# 01_POWER.net
KiCad netlist of a schematic drawn in Altium Designer
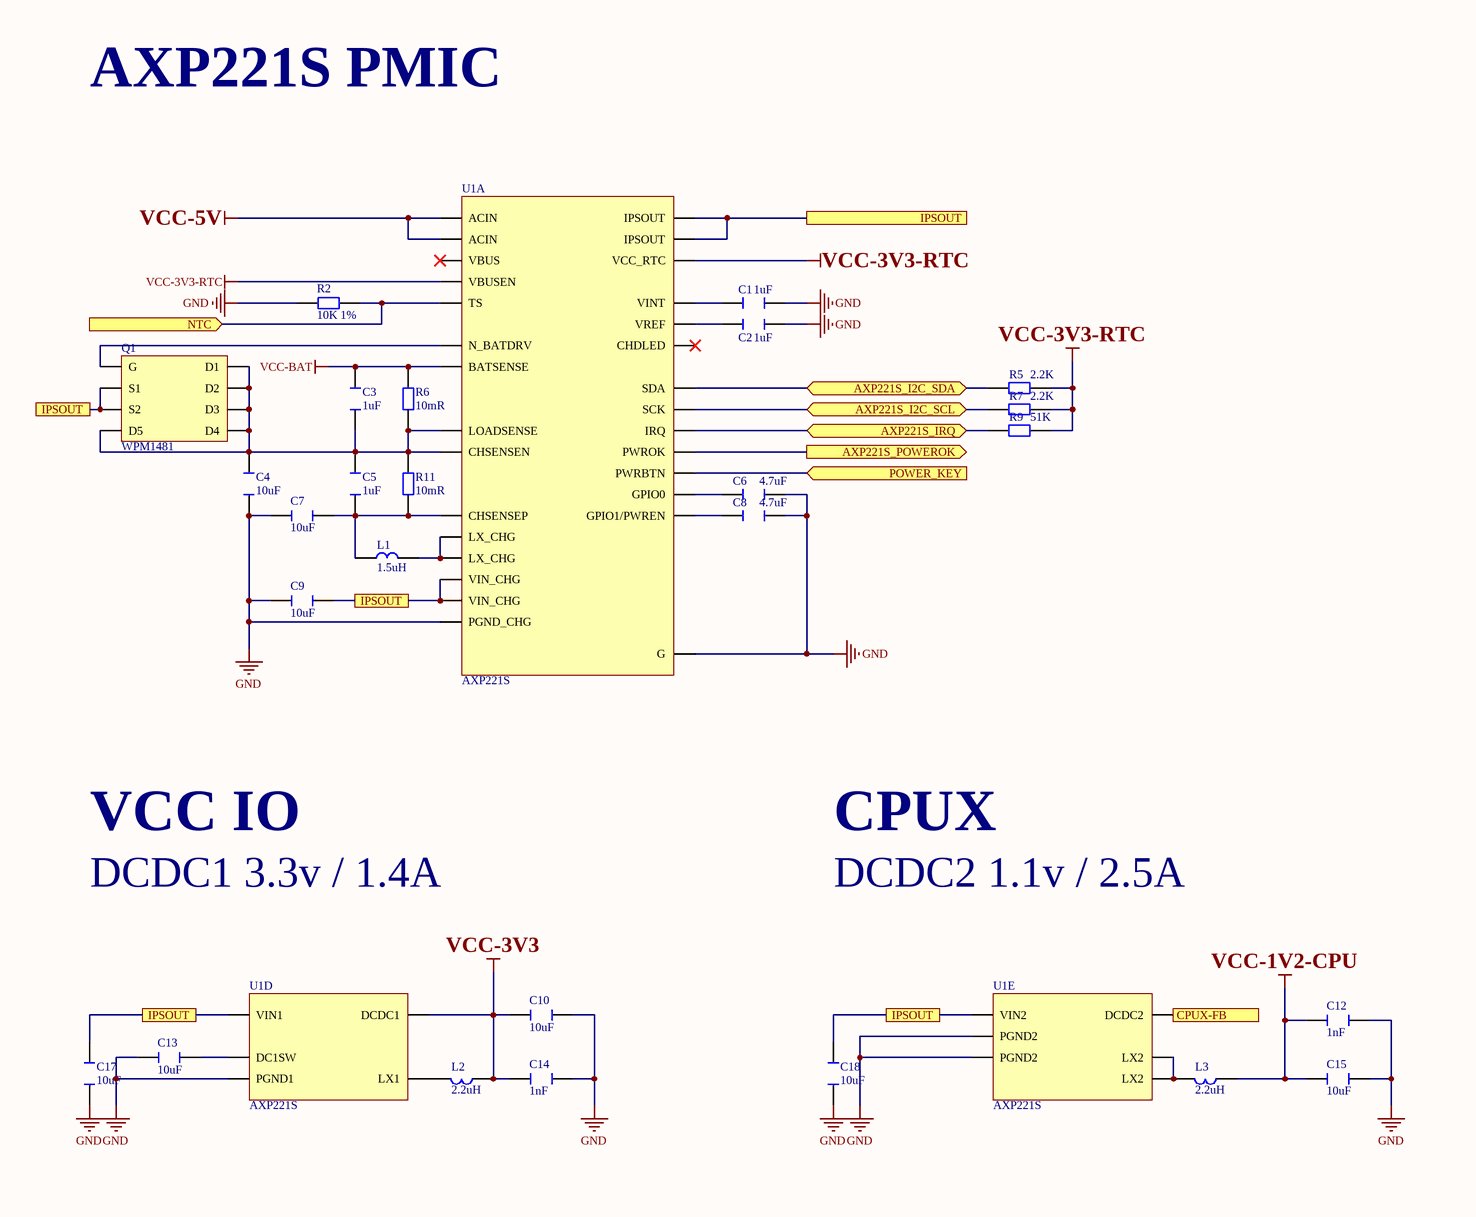
[diagram p0: 01_POWER.SchDoc, top left]
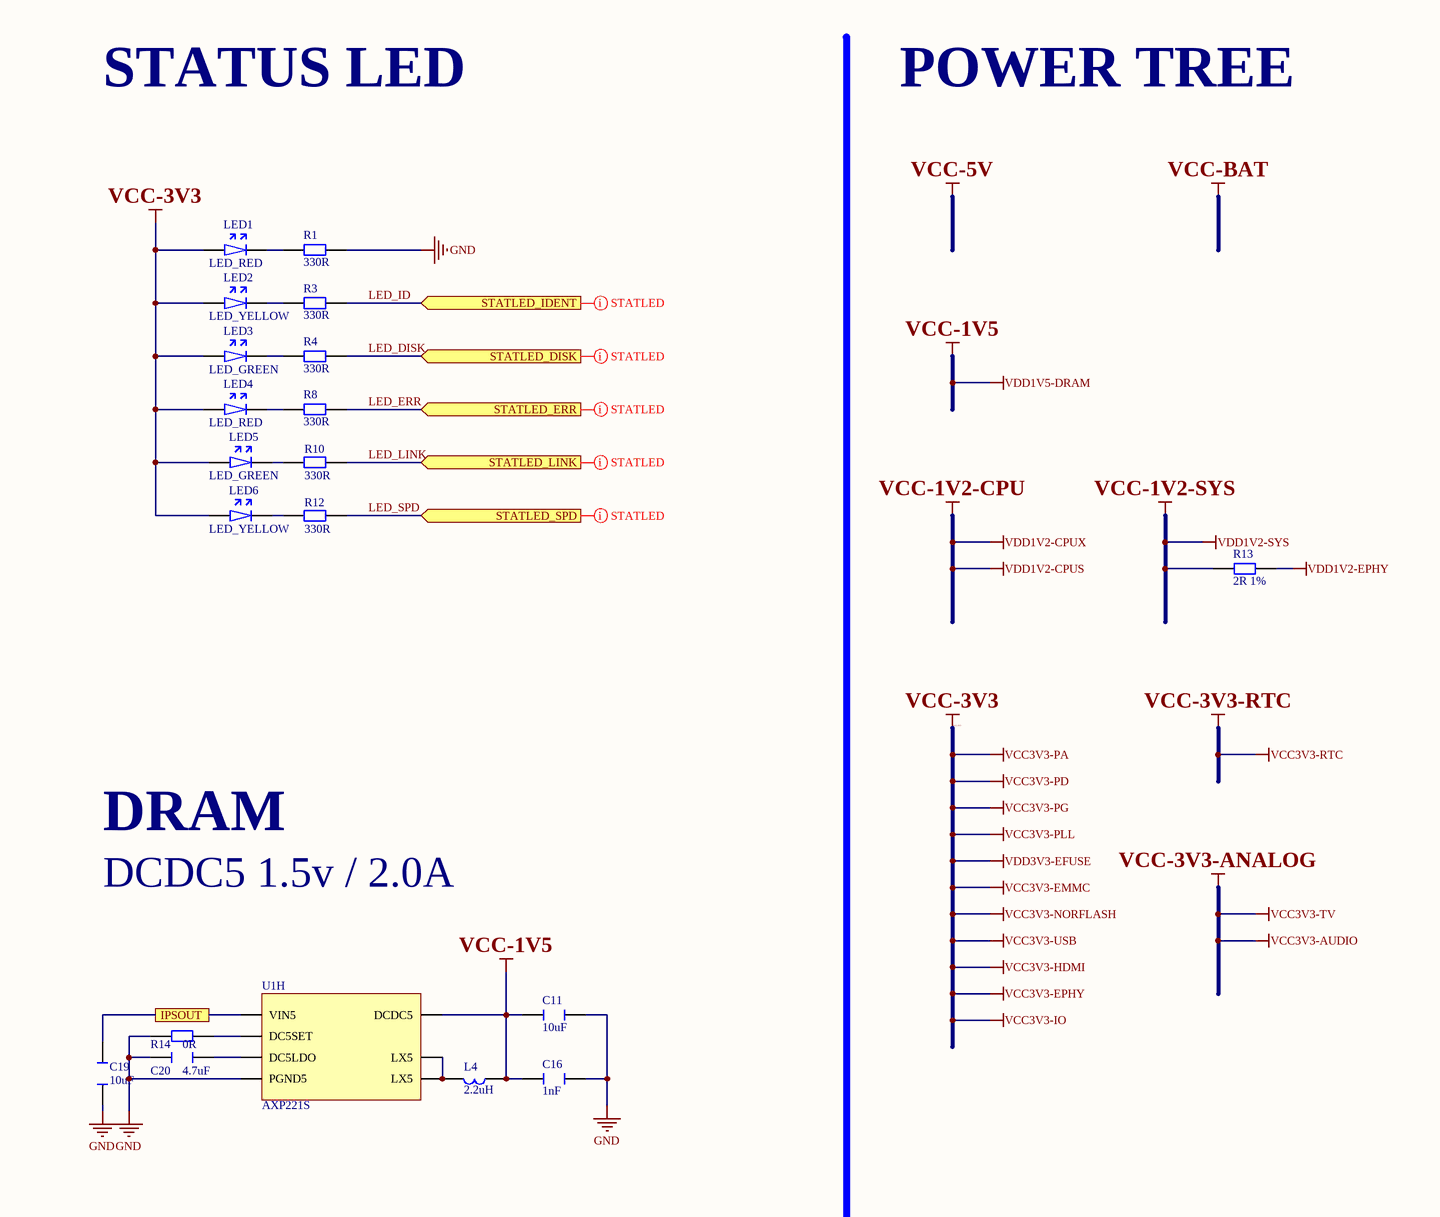
[diagram p1: 01_POWER.SchDoc, top right]
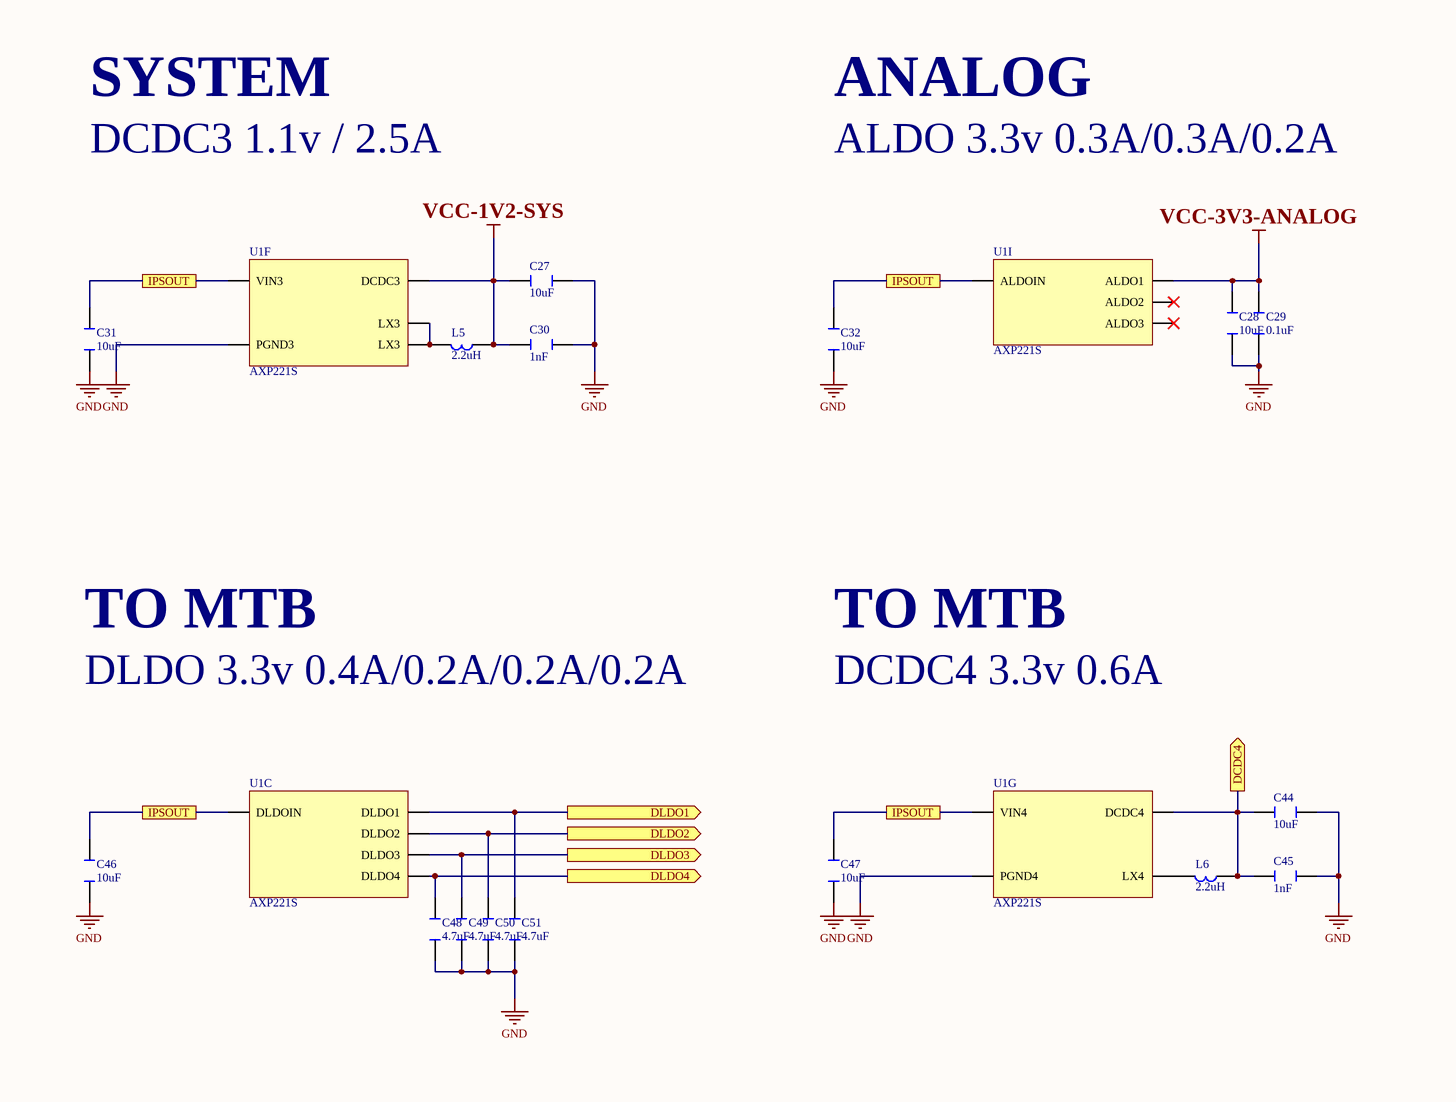
[diagram p2: 01_POWER.SchDoc, bottom left]
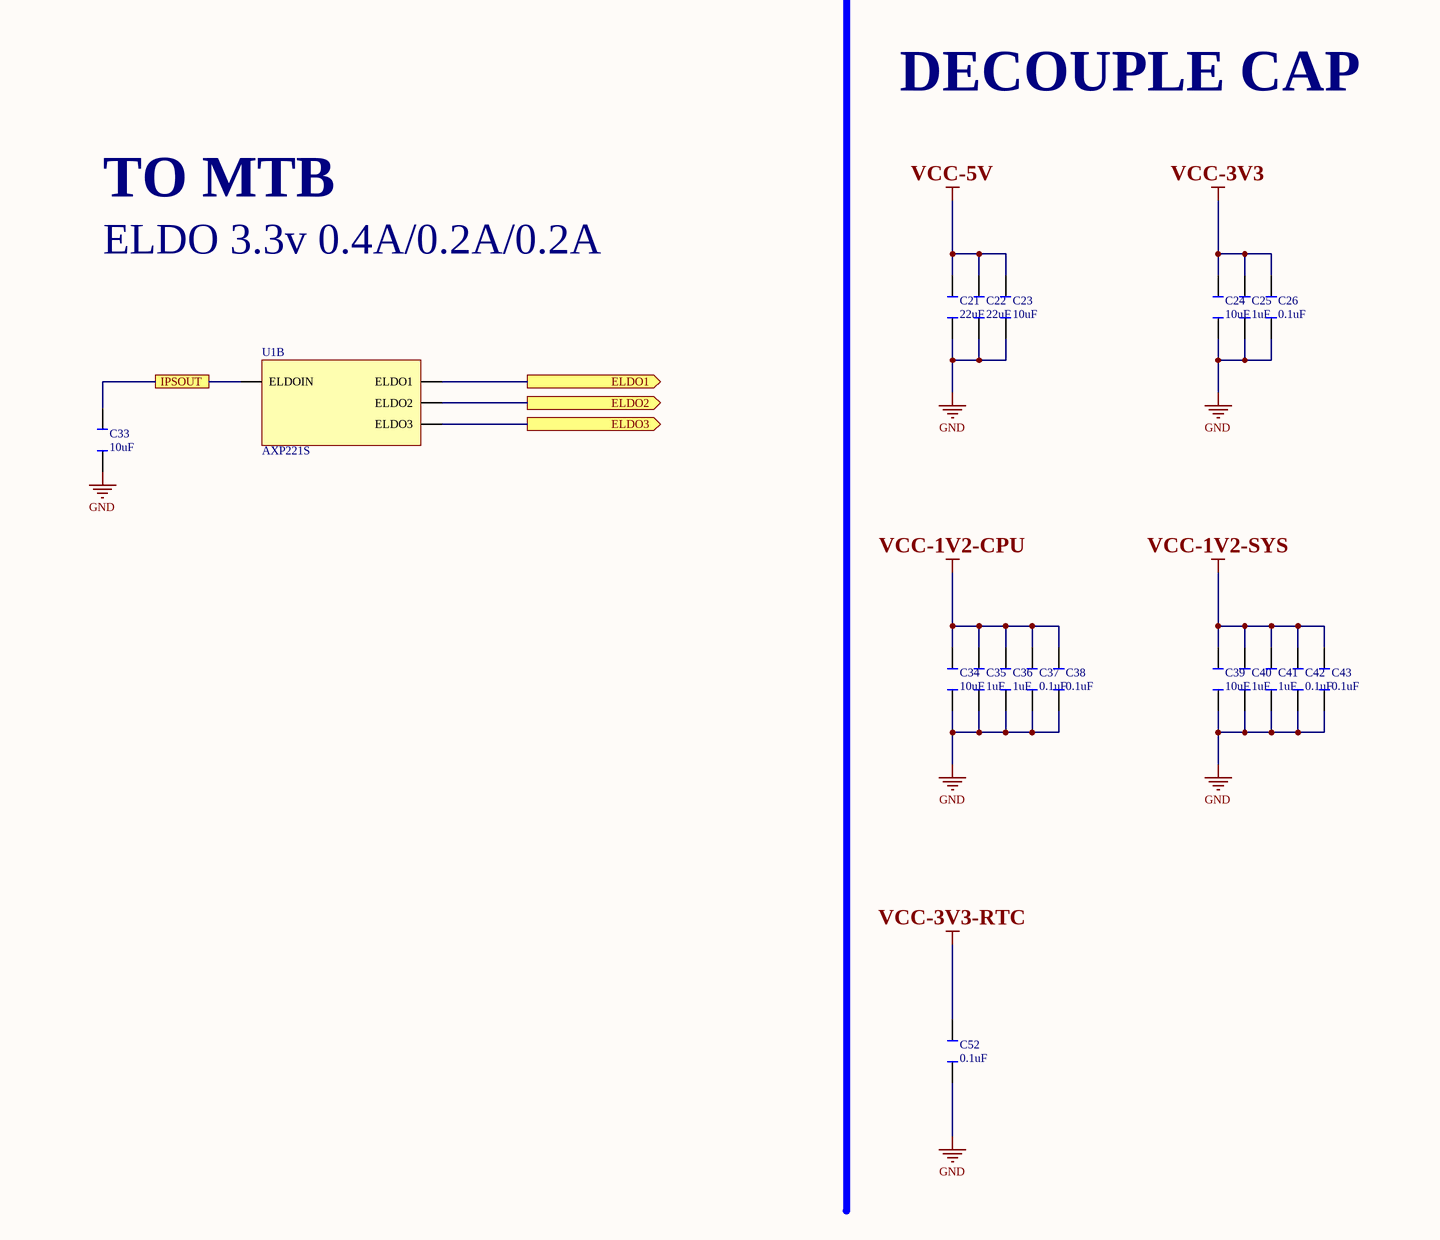
[diagram p3: 01_POWER.SchDoc, bottom right]

(export (version "E")
  (design (tool "Eeschema 10.0.6"))
  (components
    (comp (ref "C1") (value "1uF") (footprint "C0603") (libsource (lib "Board") (part "C_1UF")))
    (comp (ref "C2") (value "1uF") (footprint "C0603") (libsource (lib "Board") (part "C_1UF")))
    (comp (ref "C3") (value "1uF") (footprint "C0603") (libsource (lib "Board") (part "C_1UF")))
    (comp (ref "C4") (value "10uF") (footprint "C0603") (libsource (lib "Board") (part "C_10UF")))
    (comp (ref "C5") (value "1uF") (footprint "C0603") (libsource (lib "Board") (part "C_1UF")))
    (comp (ref "C6") (value "4.7uF") (footprint "C0402") (libsource (lib "Board") (part "C_4.7UF")))
    (comp (ref "C7") (value "10uF") (footprint "C0603") (libsource (lib "Board") (part "C_10UF")))
    (comp (ref "C8") (value "4.7uF") (footprint "C0402") (libsource (lib "Board") (part "C_4.7UF")))
    (comp (ref "C9") (value "10uF") (footprint "C0603") (libsource (lib "Board") (part "C_10UF")))
    (comp (ref "C10") (value "10uF") (footprint "C0603") (libsource (lib "Board") (part "C_10UF")))
    (comp (ref "C11") (value "10uF") (footprint "C0603") (libsource (lib "Board") (part "C_10UF")))
    (comp (ref "C12") (value "1nF") (footprint "C0603") (libsource (lib "Board") (part "C_1NF")))
    (comp (ref "C13") (value "10uF") (footprint "C0603") (libsource (lib "Board") (part "C_10UF")))
    (comp (ref "C14") (value "1nF") (footprint "C0603") (libsource (lib "Board") (part "C_1NF")))
    (comp (ref "C15") (value "10uF") (footprint "C0603") (libsource (lib "Board") (part "C_10UF")))
    (comp (ref "C16") (value "1nF") (footprint "C0603") (libsource (lib "Board") (part "C_1NF")))
    (comp (ref "C17") (value "10uF") (footprint "C0603") (libsource (lib "Board") (part "C_10UF")))
    (comp (ref "C18") (value "10uF") (footprint "C0603") (libsource (lib "Board") (part "C_10UF")))
    (comp (ref "C19") (value "10uF") (footprint "C0603") (libsource (lib "Board") (part "C_10UF")))
    (comp (ref "C20") (value "4.7uF") (footprint "C0603") (libsource (lib "Board") (part "C_4.7UF")))
    (comp (ref "C21") (value "22uF") (footprint "C0603") (libsource (lib "Board") (part "C_22UF")))
    (comp (ref "C22") (value "22uF") (footprint "C0603") (libsource (lib "Board") (part "C_22UF")))
    (comp (ref "C23") (value "10uF") (footprint "C0603") (libsource (lib "Board") (part "C_10UF")))
    (comp (ref "C24") (value "10uF") (footprint "C0603") (libsource (lib "Board") (part "C_10UF")))
    (comp (ref "C25") (value "1uF") (footprint "C0402") (libsource (lib "Board") (part "C_1UF")))
    (comp (ref "C26") (value "0.1uF") (footprint "C0603") (libsource (lib "Board") (part "C_0.1UF")))
    (comp (ref "C27") (value "10uF") (footprint "C0603") (libsource (lib "Board") (part "C_10UF")))
    (comp (ref "C28") (value "10uF") (footprint "C0603") (libsource (lib "Board") (part "C_10UF")))
    (comp (ref "C29") (value "0.1uF") (footprint "C0603") (libsource (lib "Board") (part "C_0.1UF")))
    (comp (ref "C30") (value "1nF") (footprint "C0603") (libsource (lib "Board") (part "C_1NF")))
    (comp (ref "C31") (value "10uF") (footprint "C0603") (libsource (lib "Board") (part "C_10UF")))
    (comp (ref "C32") (value "10uF") (footprint "C0603") (libsource (lib "Board") (part "C_10UF")))
    (comp (ref "C33") (value "10uF") (footprint "C0603") (libsource (lib "Board") (part "C_10UF")))
    (comp (ref "C34") (value "10uF") (footprint "C0603") (libsource (lib "Board") (part "C_10UF")))
    (comp (ref "C35") (value "1uF") (footprint "C0603") (libsource (lib "Board") (part "C_1UF")))
    (comp (ref "C36") (value "1uF") (footprint "C0603") (libsource (lib "Board") (part "C_1UF")))
    (comp (ref "C37") (value "0.1uF") (footprint "C0402") (libsource (lib "Board") (part "C_0.1UF")))
    (comp (ref "C38") (value "0.1uF") (footprint "C0402") (libsource (lib "Board") (part "C_0.1UF")))
    (comp (ref "C39") (value "10uF") (footprint "C0603") (libsource (lib "Board") (part "C_10UF")))
    (comp (ref "C40") (value "1uF") (footprint "C0402") (libsource (lib "Board") (part "C_1UF")))
    (comp (ref "C41") (value "1uF") (footprint "C0603") (libsource (lib "Board") (part "C_1UF")))
    (comp (ref "C42") (value "0.1uF") (footprint "C0402") (libsource (lib "Board") (part "C_0.1UF")))
    (comp (ref "C43") (value "0.1uF") (footprint "C0402") (libsource (lib "Board") (part "C_0.1UF")))
    (comp (ref "C44") (value "10uF") (footprint "C0603") (libsource (lib "Board") (part "C_10UF")))
    (comp (ref "C45") (value "1nF") (footprint "C0603") (libsource (lib "Board") (part "C_1NF")))
    (comp (ref "C46") (value "10uF") (footprint "C0603") (libsource (lib "Board") (part "C_10UF")))
    (comp (ref "C47") (value "10uF") (footprint "C0603") (libsource (lib "Board") (part "C_10UF")))
    (comp (ref "C48") (value "4.7uF") (footprint "C0603") (libsource (lib "Board") (part "C_4.7UF")))
    (comp (ref "C49") (value "4.7uF") (footprint "C0603") (libsource (lib "Board") (part "C_4.7UF")))
    (comp (ref "C50") (value "4.7uF") (footprint "C0603") (libsource (lib "Board") (part "C_4.7UF")))
    (comp (ref "C51") (value "4.7uF") (footprint "C0603") (libsource (lib "Board") (part "C_4.7UF")))
    (comp (ref "C52") (value "0.1uF") (footprint "C0402") (libsource (lib "Board") (part "C_0.1UF")))
    (comp (ref "L1") (value "1.5uH") (footprint "L2520") (libsource (lib "Board") (part "L_1.5UH")))
    (comp (ref "L2") (value "2.2uH") (footprint "L2520") (libsource (lib "Board") (part "L_2.2UH")))
    (comp (ref "L3") (value "2.2uH") (footprint "L2520") (libsource (lib "Board") (part "L_2.2UH")))
    (comp (ref "L4") (value "2.2uH") (footprint "L2520") (libsource (lib "Board") (part "L_2.2UH")))
    (comp (ref "L5") (value "2.2uH") (footprint "L2520") (libsource (lib "Board") (part "L_2.2UH")))
    (comp (ref "L6") (value "2.2uH") (footprint "L2520") (libsource (lib "Board") (part "L_2.2UH")))
    (comp (ref "LED1") (value "LED_RED") (footprint "LED0603_RED") (libsource (lib "Board") (part "LED_RED")))
    (comp (ref "LED2")
      (value "LED_YELLOW")
      (footprint "LED0603_YELLOW")
      (libsource (lib "Board") (part "LED_YELLOW"))
    )
    (comp (ref "LED3")
      (value "LED_GREEN")
      (footprint "LED0603_GREEN")
      (libsource (lib "Board") (part "LED_GREEN"))
    )
    (comp (ref "LED4") (value "LED_RED") (footprint "LED0603_RED") (libsource (lib "Board") (part "LED_RED")))
    (comp (ref "LED5")
      (value "LED_GREEN")
      (footprint "LED0603_GREEN")
      (libsource (lib "Board") (part "LED_GREEN"))
    )
    (comp (ref "LED6")
      (value "LED_YELLOW")
      (footprint "LED0603_YELLOW")
      (libsource (lib "Board") (part "LED_YELLOW"))
    )
    (comp (ref "Q1") (value "WPM1481") (footprint "WPM1481") (libsource (lib "Board") (part "WPM1481")))
    (comp (ref "R1") (value "330R") (footprint "R0402") (libsource (lib "Board") (part "R_330R")))
    (comp (ref "R2") (value "10K 1%") (footprint "R0402") (libsource (lib "Board") (part "R_10K_P1")))
    (comp (ref "R3") (value "330R") (footprint "R0402") (libsource (lib "Board") (part "R_330R")))
    (comp (ref "R4") (value "330R") (footprint "R0402") (libsource (lib "Board") (part "R_330R")))
    (comp (ref "R5") (value "2.2K") (footprint "R0402") (libsource (lib "Board") (part "R_2.2K")))
    (comp (ref "R6") (value "10mR") (footprint "R0805") (libsource (lib "Board") (part "R_10mR")))
    (comp (ref "R7") (value "2.2K") (footprint "R0402") (libsource (lib "Board") (part "R_2.2K")))
    (comp (ref "R8") (value "330R") (footprint "R0402") (libsource (lib "Board") (part "R_330R")))
    (comp (ref "R9") (value "51K") (footprint "R0402") (libsource (lib "Board") (part "R_51K")))
    (comp (ref "R10") (value "330R") (footprint "R0402") (libsource (lib "Board") (part "R_330R")))
    (comp (ref "R11") (value "10mR") (footprint "R0805") (libsource (lib "Board") (part "R_10mR")))
    (comp (ref "R12") (value "330R") (footprint "R0402") (libsource (lib "Board") (part "R_330R")))
    (comp (ref "R13") (value "2R 1%") (footprint "R0402") (libsource (lib "Board") (part "R_2R_P1")))
    (comp (ref "R14") (value "0R") (footprint "R0402") (libsource (lib "Board") (part "R_0R")))
    (comp (ref "U1") (value "AXP221S") (footprint "AXP221S") (libsource (lib "Board") (part "AXP221S")))
  )
  (nets
    (net (code "1") (name "/AXP221S_I2C_SCL") (class "Default")
      (node (ref "R7") (pin "1") (pinfunction "17_1") (pintype "passive"))
      (node (ref "U1") (pin "44") (pinfunction "SCK_44") (pintype "passive"))
    )
    (net (code "2") (name "/AXP221S_I2C_SDA") (class "Default")
      (node (ref "R5") (pin "1") (pinfunction "17_1") (pintype "passive"))
      (node (ref "U1") (pin "45") (pinfunction "SDA_45") (pintype "passive"))
    )
    (net (code "3") (name "/AXP221S_IRQ") (class "Default")
      (node (ref "R9") (pin "1") (pinfunction "17_1") (pintype "passive"))
      (node (ref "U1") (pin "29") (pinfunction "IRQ_29") (pintype "passive"))
    )
    (net (code "4") (name "/AXP221S_POWEROK") (class "Default")
      (node (ref "U1") (pin "43") (pinfunction "PWROK_43") (pintype "passive"))
    )
    (net (code "5") (name "/CPUX-FB") (class "Default")
      (node (ref "U1") (pin "28") (pinfunction "DCDC2_28") (pintype "passive"))
    )
    (net (code "6") (name "/DCDC4") (class "Default")
      (node (ref "C44") (pin "1") (pinfunction "17_1") (pintype "passive"))
      (node (ref "C45") (pin "1") (pinfunction "17_1") (pintype "passive"))
      (node (ref "L6") (pin "1") (pinfunction "17_1") (pintype "passive"))
      (node (ref "U1") (pin "67") (pinfunction "DCDC4_67") (pintype "passive"))
    )
    (net (code "7") (name "/DLDO1") (class "Default")
      (node (ref "C51") (pin "2") (pinfunction "18_2") (pintype "passive"))
      (node (ref "U1") (pin "19") (pinfunction "DLDO1_19") (pintype "passive"))
    )
    (net (code "8") (name "/DLDO2") (class "Default")
      (node (ref "C50") (pin "2") (pinfunction "18_2") (pintype "passive"))
      (node (ref "U1") (pin "17") (pinfunction "DLDO2_17") (pintype "passive"))
    )
    (net (code "9") (name "/DLDO3") (class "Default")
      (node (ref "C49") (pin "2") (pinfunction "18_2") (pintype "passive"))
      (node (ref "U1") (pin "16") (pinfunction "DLDO3_16") (pintype "passive"))
    )
    (net (code "10") (name "/DLDO4") (class "Default")
      (node (ref "C48") (pin "2") (pinfunction "18_2") (pintype "passive"))
      (node (ref "U1") (pin "20") (pinfunction "DLDO4_20") (pintype "passive"))
    )
    (net (code "11") (name "/ELDO1") (class "Default")
      (node (ref "U1") (pin "68") (pinfunction "ELDO1_68") (pintype "passive"))
    )
    (net (code "12") (name "/ELDO2") (class "Default")
      (node (ref "U1") (pin "2") (pinfunction "ELDO2_2") (pintype "passive"))
    )
    (net (code "13") (name "/ELDO3") (class "Default")
      (node (ref "U1") (pin "3") (pinfunction "ELDO3_3") (pintype "passive"))
    )
    (net (code "14") (name "/IPSOUT") (class "Default")
      (node (ref "C17") (pin "1") (pinfunction "17_1") (pintype "passive"))
      (node (ref "C18") (pin "1") (pinfunction "17_1") (pintype "passive"))
      (node (ref "C19") (pin "1") (pinfunction "17_1") (pintype "passive"))
      (node (ref "C31") (pin "1") (pinfunction "17_1") (pintype "passive"))
      (node (ref "C32") (pin "1") (pinfunction "17_1") (pintype "passive"))
      (node (ref "C33") (pin "1") (pinfunction "17_1") (pintype "passive"))
      (node (ref "C46") (pin "1") (pinfunction "17_1") (pintype "passive"))
      (node (ref "C47") (pin "1") (pinfunction "17_1") (pintype "passive"))
      (node (ref "C9") (pin "2") (pinfunction "18_2") (pintype "passive"))
      (node (ref "Q1") (pin "4") (pinfunction "S1_4") (pintype "passive"))
      (node (ref "Q1") (pin "7") (pinfunction "S2_7") (pintype "passive"))
      (node (ref "U1") (pin "1") (pinfunction "ELDOIN_1") (pintype "passive"))
      (node (ref "U1") (pin "13") (pinfunction "VIN1_13") (pintype "passive"))
      (node (ref "U1") (pin "18") (pinfunction "DLDOIN_18") (pintype "passive"))
      (node (ref "U1") (pin "23") (pinfunction "VIN2_23") (pintype "passive"))
      (node (ref "U1") (pin "33") (pinfunction "ALDOIN_33") (pintype "passive"))
      (node (ref "U1") (pin "39") (pinfunction "VIN3_39") (pintype "passive"))
      (node (ref "U1") (pin "53") (pinfunction "IPSOUT_53") (pintype "passive"))
      (node (ref "U1") (pin "54") (pinfunction "IPSOUT_54") (pintype "passive"))
      (node (ref "U1") (pin "62") (pinfunction "VIN_CHG_62") (pintype "passive"))
      (node (ref "U1") (pin "63") (pinfunction "VIN_CHG_63") (pintype "passive"))
      (node (ref "U1") (pin "64") (pinfunction "VIN4_64") (pintype "passive"))
      (node (ref "U1") (pin "9") (pinfunction "VIN5_9") (pintype "passive"))
    )
    (net (code "15") (name "/LED_DISK") (class "Default")
      (node (ref "R4") (pin "2") (pinfunction "18_2") (pintype "passive"))
    )
    (net (code "16") (name "/LED_ERR") (class "Default")
      (node (ref "R8") (pin "2") (pinfunction "18_2") (pintype "passive"))
    )
    (net (code "17") (name "/LED_ID") (class "Default")
      (node (ref "R3") (pin "2") (pinfunction "18_2") (pintype "passive"))
    )
    (net (code "18") (name "/LED_LINK") (class "Default")
      (node (ref "R10") (pin "1") (pinfunction "17_1") (pintype "passive"))
    )
    (net (code "19") (name "/LED_SPD") (class "Default")
      (node (ref "R12") (pin "1") (pinfunction "17_1") (pintype "passive"))
    )
    (net (code "20") (name "/NTC") (class "Default")
      (node (ref "R2") (pin "2") (pinfunction "18_2") (pintype "passive"))
      (node (ref "U1") (pin "30") (pinfunction "TS_30") (pintype "passive"))
    )
    (net (code "21") (name "/POWER_KEY") (class "Default")
      (node (ref "U1") (pin "12") (pinfunction "PWRBTN_12") (pintype "passive"))
    )
    (net (code "22") (name "GND") (class "Default")
      (node (ref "C1") (pin "2") (pinfunction "18_2") (pintype "passive"))
      (node (ref "C10") (pin "2") (pinfunction "18_2") (pintype "passive"))
      (node (ref "C11") (pin "2") (pinfunction "18_2") (pintype "passive"))
      (node (ref "C12") (pin "2") (pinfunction "18_2") (pintype "passive"))
      (node (ref "C13") (pin "1") (pinfunction "17_1") (pintype "passive"))
      (node (ref "C14") (pin "1") (pinfunction "17_1") (pintype "passive"))
      (node (ref "C15") (pin "2") (pinfunction "18_2") (pintype "passive"))
      (node (ref "C16") (pin "2") (pinfunction "18_2") (pintype "passive"))
      (node (ref "C17") (pin "2") (pinfunction "18_2") (pintype "passive"))
      (node (ref "C18") (pin "2") (pinfunction "18_2") (pintype "passive"))
      (node (ref "C19") (pin "2") (pinfunction "18_2") (pintype "passive"))
      (node (ref "C2") (pin "2") (pinfunction "18_2") (pintype "passive"))
      (node (ref "C20") (pin "2") (pinfunction "18_2") (pintype "passive"))
      (node (ref "C21") (pin "1") (pinfunction "17_1") (pintype "passive"))
      (node (ref "C22") (pin "1") (pinfunction "17_1") (pintype "passive"))
      (node (ref "C23") (pin "1") (pinfunction "17_1") (pintype "passive"))
      (node (ref "C24") (pin "1") (pinfunction "17_1") (pintype "passive"))
      (node (ref "C25") (pin "1") (pinfunction "17_1") (pintype "passive"))
      (node (ref "C26") (pin "1") (pinfunction "17_1") (pintype "passive"))
      (node (ref "C27") (pin "2") (pinfunction "18_2") (pintype "passive"))
      (node (ref "C28") (pin "2") (pinfunction "18_2") (pintype "passive"))
      (node (ref "C29") (pin "1") (pinfunction "17_1") (pintype "passive"))
      (node (ref "C30") (pin "2") (pinfunction "18_2") (pintype "passive"))
      (node (ref "C31") (pin "2") (pinfunction "18_2") (pintype "passive"))
      (node (ref "C32") (pin "2") (pinfunction "18_2") (pintype "passive"))
      (node (ref "C33") (pin "2") (pinfunction "18_2") (pintype "passive"))
      (node (ref "C34") (pin "1") (pinfunction "17_1") (pintype "passive"))
      (node (ref "C35") (pin "1") (pinfunction "17_1") (pintype "passive"))
      (node (ref "C36") (pin "1") (pinfunction "17_1") (pintype "passive"))
      (node (ref "C37") (pin "1") (pinfunction "17_1") (pintype "passive"))
      (node (ref "C38") (pin "1") (pinfunction "17_1") (pintype "passive"))
      (node (ref "C39") (pin "1") (pinfunction "17_1") (pintype "passive"))
      (node (ref "C4") (pin "1") (pinfunction "17_1") (pintype "passive"))
      (node (ref "C40") (pin "1") (pinfunction "17_1") (pintype "passive"))
      (node (ref "C41") (pin "1") (pinfunction "17_1") (pintype "passive"))
      (node (ref "C42") (pin "1") (pinfunction "17_1") (pintype "passive"))
      (node (ref "C43") (pin "1") (pinfunction "17_1") (pintype "passive"))
      (node (ref "C44") (pin "2") (pinfunction "18_2") (pintype "passive"))
      (node (ref "C45") (pin "2") (pinfunction "18_2") (pintype "passive"))
      (node (ref "C46") (pin "2") (pinfunction "18_2") (pintype "passive"))
      (node (ref "C47") (pin "2") (pinfunction "18_2") (pintype "passive"))
      (node (ref "C48") (pin "1") (pinfunction "17_1") (pintype "passive"))
      (node (ref "C49") (pin "1") (pinfunction "17_1") (pintype "passive"))
      (node (ref "C50") (pin "1") (pinfunction "17_1") (pintype "passive"))
      (node (ref "C51") (pin "1") (pinfunction "17_1") (pintype "passive"))
      (node (ref "C52") (pin "1") (pinfunction "17_1") (pintype "passive"))
      (node (ref "C6") (pin "2") (pinfunction "18_2") (pintype "passive"))
      (node (ref "C7") (pin "1") (pinfunction "17_1") (pintype "passive"))
      (node (ref "C8") (pin "2") (pinfunction "18_2") (pintype "passive"))
      (node (ref "C9") (pin "1") (pinfunction "17_1") (pintype "passive"))
      (node (ref "R1") (pin "2") (pinfunction "18_2") (pintype "passive"))
      (node (ref "R14") (pin "1") (pinfunction "17_1") (pintype "passive"))
      (node (ref "R2") (pin "1") (pinfunction "17_1") (pintype "passive"))
      (node (ref "U1") (pin "15") (pinfunction "PGND1_15") (pintype "passive"))
      (node (ref "U1") (pin "26") (pinfunction "PGND2_26") (pintype "passive"))
      (node (ref "U1") (pin "27") (pinfunction "PGND2_27") (pintype "passive"))
      (node (ref "U1") (pin "42") (pinfunction "PGND3_42") (pintype "passive"))
      (node (ref "U1") (pin "59") (pinfunction "PGND_CHG_59") (pintype "passive"))
      (node (ref "U1") (pin "6") (pinfunction "PGND5_6") (pintype "passive"))
      (node (ref "U1") (pin "66") (pinfunction "PGND4_66") (pintype "passive"))
      (node (ref "U1") (pin "69") (pinfunction "G_69") (pintype "passive"))
    )
    (net (code "23") (name "Net-(C1-17)") (class "Default")
      (node (ref "C1") (pin "1") (pinfunction "17_1") (pintype "passive"))
      (node (ref "U1") (pin "47") (pinfunction "VINT_47") (pintype "passive"))
    )
    (net (code "24") (name "Net-(C2-17)") (class "Default")
      (node (ref "C2") (pin "1") (pinfunction "17_1") (pintype "passive"))
      (node (ref "U1") (pin "35") (pinfunction "VREF_35") (pintype "passive"))
    )
    (net (code "25") (name "Net-(C3-17)") (class "Default")
      (node (ref "C3") (pin "1") (pinfunction "17_1") (pintype "passive"))
      (node (ref "C4") (pin "2") (pinfunction "18_2") (pintype "passive"))
      (node (ref "C5") (pin "2") (pinfunction "18_2") (pintype "passive"))
      (node (ref "Q1") (pin "1") (pinfunction "D1_1") (pintype "passive"))
      (node (ref "Q1") (pin "2") (pinfunction "D2_2") (pintype "passive"))
      (node (ref "Q1") (pin "5") (pinfunction "D3_5") (pintype "passive"))
      (node (ref "Q1") (pin "6") (pinfunction "D4_6") (pintype "passive"))
      (node (ref "Q1") (pin "8") (pinfunction "D5_8") (pintype "passive"))
      (node (ref "R11") (pin "2") (pinfunction "18_2") (pintype "passive"))
      (node (ref "R6") (pin "1") (pinfunction "17_1") (pintype "passive"))
      (node (ref "U1") (pin "50") (pinfunction "LOADSENSE_50") (pintype "passive"))
      (node (ref "U1") (pin "58") (pinfunction "CHSENSEN_58") (pintype "passive"))
    )
    (net (code "26") (name "Net-(C5-17)") (class "Default")
      (node (ref "C5") (pin "1") (pinfunction "17_1") (pintype "passive"))
      (node (ref "C7") (pin "2") (pinfunction "18_2") (pintype "passive"))
      (node (ref "L1") (pin "1") (pinfunction "17_1") (pintype "passive"))
      (node (ref "R11") (pin "1") (pinfunction "17_1") (pintype "passive"))
      (node (ref "U1") (pin "57") (pinfunction "CHSENSEP_57") (pintype "passive"))
    )
    (net (code "27") (name "Net-(C6-17)") (class "Default")
      (node (ref "C6") (pin "1") (pinfunction "17_1") (pintype "passive"))
      (node (ref "U1") (pin "37") (pinfunction "GPIO0_37") (pintype "passive"))
    )
    (net (code "28") (name "Net-(C8-17)") (class "Default")
      (node (ref "C8") (pin "1") (pinfunction "17_1") (pintype "passive"))
      (node (ref "U1") (pin "31") (pinfunction "GPIO1/PWREN_31") (pintype "passive"))
    )
    (net (code "29") (name "Net-(C13-18)") (class "Default")
      (node (ref "C13") (pin "2") (pinfunction "18_2") (pintype "passive"))
      (node (ref "U1") (pin "22") (pinfunction "DC1SW_22") (pintype "passive"))
    )
    (net (code "30") (name "Net-(C20-17)") (class "Default")
      (node (ref "C20") (pin "1") (pinfunction "17_1") (pintype "passive"))
      (node (ref "U1") (pin "4") (pinfunction "DC5LDO_4") (pintype "passive"))
    )
    (net (code "31") (name "Net-(L1-18)") (class "Default")
      (node (ref "L1") (pin "2") (pinfunction "18_2") (pintype "passive"))
      (node (ref "U1") (pin "60") (pinfunction "LX_CHG_60") (pintype "passive"))
      (node (ref "U1") (pin "61") (pinfunction "LX_CHG_61") (pintype "passive"))
    )
    (net (code "32") (name "Net-(L2-18)") (class "Default")
      (node (ref "L2") (pin "2") (pinfunction "18_2") (pintype "passive"))
      (node (ref "U1") (pin "14") (pinfunction "LX1_14") (pintype "passive"))
    )
    (net (code "33") (name "Net-(L3-18)") (class "Default")
      (node (ref "L3") (pin "2") (pinfunction "18_2") (pintype "passive"))
      (node (ref "U1") (pin "24") (pinfunction "LX2_24") (pintype "passive"))
      (node (ref "U1") (pin "25") (pinfunction "LX2_25") (pintype "passive"))
    )
    (net (code "34") (name "Net-(L4-18)") (class "Default")
      (node (ref "L4") (pin "2") (pinfunction "18_2") (pintype "passive"))
      (node (ref "U1") (pin "7") (pinfunction "LX5_7") (pintype "passive"))
      (node (ref "U1") (pin "8") (pinfunction "LX5_8") (pintype "passive"))
    )
    (net (code "35") (name "Net-(L5-18)") (class "Default")
      (node (ref "L5") (pin "2") (pinfunction "18_2") (pintype "passive"))
      (node (ref "U1") (pin "40") (pinfunction "LX3_40") (pintype "passive"))
      (node (ref "U1") (pin "41") (pinfunction "LX3_41") (pintype "passive"))
    )
    (net (code "36") (name "Net-(L6-18)") (class "Default")
      (node (ref "L6") (pin "2") (pinfunction "18_2") (pintype "passive"))
      (node (ref "U1") (pin "65") (pinfunction "LX4_65") (pintype "passive"))
    )
    (net (code "37") (name "Net-(Q1-G)") (class "Default")
      (node (ref "Q1") (pin "3") (pinfunction "G_3") (pintype "passive"))
      (node (ref "U1") (pin "51") (pinfunction "N_BATDRV_51") (pintype "passive"))
    )
    (net (code "38") (name "Net-(R1-17)") (class "Default")
      (node (ref "LED1") (pin "2") (pinfunction "2_2") (pintype "passive"))
      (node (ref "R1") (pin "1") (pinfunction "17_1") (pintype "passive"))
    )
    (net (code "39") (name "Net-(R3-17)") (class "Default")
      (node (ref "LED2") (pin "2") (pinfunction "2_2") (pintype "passive"))
      (node (ref "R3") (pin "1") (pinfunction "17_1") (pintype "passive"))
    )
    (net (code "40") (name "Net-(R4-17)") (class "Default")
      (node (ref "LED3") (pin "2") (pinfunction "2_2") (pintype "passive"))
      (node (ref "R4") (pin "1") (pinfunction "17_1") (pintype "passive"))
    )
    (net (code "41") (name "Net-(R8-17)") (class "Default")
      (node (ref "LED4") (pin "2") (pinfunction "2_2") (pintype "passive"))
      (node (ref "R8") (pin "1") (pinfunction "17_1") (pintype "passive"))
    )
    (net (code "42") (name "Net-(R10-18)") (class "Default")
      (node (ref "LED5") (pin "2") (pinfunction "2_2") (pintype "passive"))
      (node (ref "R10") (pin "2") (pinfunction "18_2") (pintype "passive"))
    )
    (net (code "43") (name "Net-(R12-18)") (class "Default")
      (node (ref "LED6") (pin "2") (pinfunction "2_2") (pintype "passive"))
      (node (ref "R12") (pin "2") (pinfunction "18_2") (pintype "passive"))
    )
    (net (code "44") (name "Net-(R14-18)") (class "Default")
      (node (ref "R14") (pin "2") (pinfunction "18_2") (pintype "passive"))
      (node (ref "U1") (pin "10") (pinfunction "DC5SET_10") (pintype "passive"))
    )
    (net (code "45") (name "VCC-1V2-CPU") (class "Default")
      (node (ref "C12") (pin "1") (pinfunction "17_1") (pintype "passive"))
      (node (ref "C15") (pin "1") (pinfunction "17_1") (pintype "passive"))
      (node (ref "C34") (pin "2") (pinfunction "18_2") (pintype "passive"))
      (node (ref "C35") (pin "2") (pinfunction "18_2") (pintype "passive"))
      (node (ref "C36") (pin "2") (pinfunction "18_2") (pintype "passive"))
      (node (ref "C37") (pin "2") (pinfunction "18_2") (pintype "passive"))
      (node (ref "C38") (pin "2") (pinfunction "18_2") (pintype "passive"))
      (node (ref "L3") (pin "1") (pinfunction "17_1") (pintype "passive"))
    )
    (net (code "46") (name "VCC-1V2-SYS") (class "Default")
      (node (ref "C27") (pin "1") (pinfunction "17_1") (pintype "passive"))
      (node (ref "C30") (pin "1") (pinfunction "17_1") (pintype "passive"))
      (node (ref "C39") (pin "2") (pinfunction "18_2") (pintype "passive"))
      (node (ref "C40") (pin "2") (pinfunction "18_2") (pintype "passive"))
      (node (ref "C41") (pin "2") (pinfunction "18_2") (pintype "passive"))
      (node (ref "C42") (pin "2") (pinfunction "18_2") (pintype "passive"))
      (node (ref "C43") (pin "2") (pinfunction "18_2") (pintype "passive"))
      (node (ref "L5") (pin "1") (pinfunction "17_1") (pintype "passive"))
      (node (ref "R13") (pin "1") (pinfunction "17_1") (pintype "passive"))
      (node (ref "U1") (pin "38") (pinfunction "DCDC3_38") (pintype "passive"))
    )
    (net (code "47") (name "VCC-1V5") (class "Default")
      (node (ref "C11") (pin "1") (pinfunction "17_1") (pintype "passive"))
      (node (ref "C16") (pin "1") (pinfunction "17_1") (pintype "passive"))
      (node (ref "L4") (pin "1") (pinfunction "17_1") (pintype "passive"))
      (node (ref "U1") (pin "5") (pinfunction "DCDC5_5") (pintype "passive"))
    )
    (net (code "48") (name "VCC-3V3") (class "Default")
      (node (ref "C10") (pin "1") (pinfunction "17_1") (pintype "passive"))
      (node (ref "C14") (pin "2") (pinfunction "18_2") (pintype "passive"))
      (node (ref "C24") (pin "2") (pinfunction "18_2") (pintype "passive"))
      (node (ref "C25") (pin "2") (pinfunction "18_2") (pintype "passive"))
      (node (ref "C26") (pin "2") (pinfunction "18_2") (pintype "passive"))
      (node (ref "L2") (pin "1") (pinfunction "17_1") (pintype "passive"))
      (node (ref "LED1") (pin "1") (pinfunction "1_1") (pintype "passive"))
      (node (ref "LED2") (pin "1") (pinfunction "1_1") (pintype "passive"))
      (node (ref "LED3") (pin "1") (pinfunction "1_1") (pintype "passive"))
      (node (ref "LED4") (pin "1") (pinfunction "1_1") (pintype "passive"))
      (node (ref "LED5") (pin "1") (pinfunction "1_1") (pintype "passive"))
      (node (ref "LED6") (pin "1") (pinfunction "1_1") (pintype "passive"))
      (node (ref "U1") (pin "21") (pinfunction "DCDC1_21") (pintype "passive"))
    )
    (net (code "49") (name "VCC-3V3-ANALOG") (class "Default")
      (node (ref "C28") (pin "1") (pinfunction "17_1") (pintype "passive"))
      (node (ref "C29") (pin "2") (pinfunction "18_2") (pintype "passive"))
      (node (ref "U1") (pin "32") (pinfunction "ALDO1_32") (pintype "passive"))
    )
    (net (code "50") (name "VCC-3V3-RTC") (class "Default")
      (node (ref "C52") (pin "2") (pinfunction "18_2") (pintype "passive"))
      (node (ref "R5") (pin "2") (pinfunction "18_2") (pintype "passive"))
      (node (ref "R7") (pin "2") (pinfunction "18_2") (pintype "passive"))
      (node (ref "R9") (pin "2") (pinfunction "18_2") (pintype "passive"))
      (node (ref "U1") (pin "11") (pinfunction "VBUSEN_11") (pintype "passive"))
      (node (ref "U1") (pin "46") (pinfunction "VCC_RTC_46") (pintype "passive"))
    )
    (net (code "51") (name "VCC-5V") (class "Default")
      (node (ref "C21") (pin "2") (pinfunction "18_2") (pintype "passive"))
      (node (ref "C22") (pin "2") (pinfunction "18_2") (pintype "passive"))
      (node (ref "C23") (pin "2") (pinfunction "18_2") (pintype "passive"))
      (node (ref "U1") (pin "55") (pinfunction "ACIN_55") (pintype "passive"))
      (node (ref "U1") (pin "56") (pinfunction "ACIN_56") (pintype "passive"))
    )
    (net (code "52") (name "VCC-BAT") (class "Default")
      (node (ref "C3") (pin "2") (pinfunction "18_2") (pintype "passive"))
      (node (ref "R6") (pin "2") (pinfunction "18_2") (pintype "passive"))
      (node (ref "U1") (pin "49") (pinfunction "BATSENSE_49") (pintype "passive"))
    )
    (net (code "53") (name "VDD1V2-EPHY") (class "Default")
      (node (ref "R13") (pin "2") (pinfunction "18_2") (pintype "passive"))
    )
    (net (code "54") (name "unconnected-(U1A-CHDLED-Pad52)") (class "Default")
      (node (ref "U1") (pin "52") (pinfunction "CHDLED_52") (pintype "passive+no_connect"))
    )
    (net (code "55") (name "unconnected-(U1A-VBUS-Pad48)") (class "Default")
      (node (ref "U1") (pin "48") (pinfunction "VBUS_48") (pintype "passive+no_connect"))
    )
    (net (code "56") (name "unconnected-(U1I-ALDO2-Pad34)") (class "Default")
      (node (ref "U1") (pin "34") (pinfunction "ALDO2_34") (pintype "passive+no_connect"))
    )
    (net (code "57") (name "unconnected-(U1I-ALDO3-Pad36)") (class "Default")
      (node (ref "U1") (pin "36") (pinfunction "ALDO3_36") (pintype "passive+no_connect"))
    )
  )
)
